# rs232.net
KiCad netlist of a schematic drawn in Altium Designer
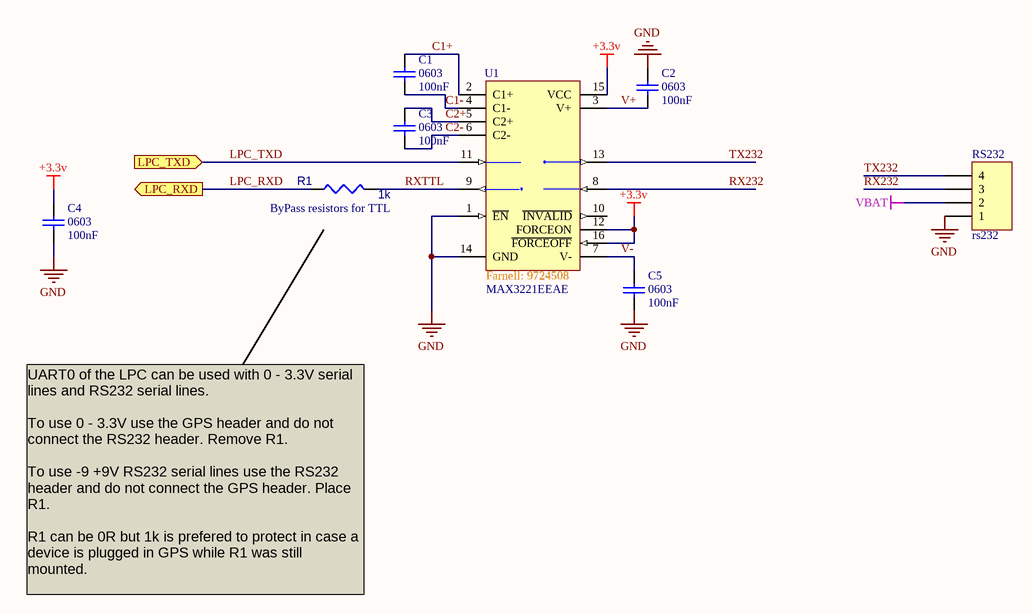
[diagram p0: rs232.SchDoc]

(export (version "E")
  (design (tool "Eeschema 10.0.6"))
  (components
    (comp (ref "C1")
      (value "0603")
      (footprint "0603")
      (description "Capacitor")
      (fields (field (name "ALTIUM_VALUE") "100nF") (field (name "PUBLISHER") "Altium Limited"))
      (libsource (lib "Miscellaneous Devices") (part "Cap"))
    )
    (comp (ref "C2")
      (value "0603")
      (footprint "0603")
      (description "Capacitor")
      (fields (field (name "ALTIUM_VALUE") "100nF") (field (name "PUBLISHER") "Altium Limited"))
      (libsource (lib "Miscellaneous Devices") (part "Cap"))
    )
    (comp (ref "C3")
      (value "0603")
      (footprint "0603")
      (description "Capacitor")
      (fields (field (name "ALTIUM_VALUE") "100nF") (field (name "PUBLISHER") "Altium Limited"))
      (libsource (lib "Miscellaneous Devices") (part "Cap"))
    )
    (comp (ref "C4")
      (value "0603")
      (footprint "0603")
      (description "Capacitor")
      (fields
        (field (name "ALTIUM_VALUE") "100nF")
        (field (name "VOLTAGE") "50V")
        (field (name "PUBLISHER") "Altium Limited")
      )
      (libsource (lib "Miscellaneous Devices") (part "Cap"))
    )
    (comp (ref "C5")
      (value "0603")
      (footprint "0603")
      (description "Capacitor")
      (fields (field (name "ALTIUM_VALUE") "100nF") (field (name "PUBLISHER") "Altium Limited"))
      (libsource (lib "Miscellaneous Devices") (part "Cap"))
    )
    (comp (ref "R1") (value "1k") (footprint "0603RES") (libsource (lib "*") (part "RES1")))
    (comp (ref "RS232")
      (value "rs232")
      (footprint "HDR4")
      (description "Header, 4-Pin")
      (fields (field (name "PUBLISHER") "Altium Limited"))
      (libsource (lib "Miscellaneous Connectors") (part "Header 4"))
    )
    (comp (ref "U1")
      (value "MAX3221EEAE")
      (footprint "SSOP16")
      (description "±15kV ESD-Protected, 1µA, 3.0V/5.5V, 250kbps, RS-232 Transceiver with AutoShutdown")
      (fields (field (name "FARNELL") "9724508") (field (name "PUBLISHER") "Altium Limited"))
      (libsource (lib "Maxim Communication Transceiver") (part "MAX3221EEAE"))
    )
  )
  (nets
    (net (code "1") (name "+3.3v") (class "Default")
      (node (ref "C4") (pin "2") (pinfunction "2_2") (pintype "passive"))
      (node (ref "U1") (pin "12") (pinfunction "FORCEON_12") (pintype "passive"))
      (node (ref "U1") (pin "15") (pinfunction "VCC_15") (pintype "power_in"))
      (node (ref "U1") (pin "16") (pinfunction "~{FORCEOFF}_16") (pintype "input"))
    )
    (net (code "2") (name "/C1+") (class "Default")
      (node (ref "C1") (pin "2") (pinfunction "2_2") (pintype "passive"))
      (node (ref "U1") (pin "2") (pinfunction "C1+_2") (pintype "passive"))
    )
    (net (code "3") (name "/C1-") (class "Default")
      (node (ref "C1") (pin "1") (pinfunction "1_1") (pintype "passive"))
      (node (ref "U1") (pin "4") (pinfunction "C1-_4") (pintype "passive"))
    )
    (net (code "4") (name "/C2+") (class "Default")
      (node (ref "C3") (pin "2") (pinfunction "2_2") (pintype "passive"))
      (node (ref "U1") (pin "5") (pinfunction "C2+_5") (pintype "passive"))
    )
    (net (code "5") (name "/C2-") (class "Default")
      (node (ref "C3") (pin "1") (pinfunction "1_1") (pintype "passive"))
      (node (ref "U1") (pin "6") (pinfunction "C2-_6") (pintype "passive"))
    )
    (net (code "6") (name "/LPC_RXD") (class "Default") (node (ref "R1") (pin "1") (pintype "passive")))
    (net (code "7") (name "/LPC_TXD") (class "Default")
      (node (ref "U1") (pin "11") (pinfunction "T1IN_11") (pintype "input"))
    )
    (net (code "8") (name "/RX232") (class "Default")
      (node (ref "RS232") (pin "3") (pinfunction "3_3") (pintype "passive"))
      (node (ref "U1") (pin "8") (pinfunction "R1IN_8") (pintype "input"))
    )
    (net (code "9") (name "/RXTTL") (class "Default")
      (node (ref "R1") (pin "2") (pintype "passive"))
      (node (ref "U1") (pin "9") (pinfunction "R1OUT_9") (pintype "output"))
    )
    (net (code "10") (name "/TX232") (class "Default")
      (node (ref "RS232") (pin "4") (pinfunction "4_4") (pintype "passive"))
      (node (ref "U1") (pin "13") (pinfunction "T1OUT_13") (pintype "output"))
    )
    (net (code "11") (name "/V+") (class "Default")
      (node (ref "C2") (pin "1") (pinfunction "1_1") (pintype "passive"))
      (node (ref "U1") (pin "3") (pinfunction "V+_3") (pintype "power_in"))
    )
    (net (code "12") (name "/V-") (class "Default")
      (node (ref "C5") (pin "2") (pinfunction "2_2") (pintype "passive"))
      (node (ref "U1") (pin "7") (pinfunction "V-_7") (pintype "power_in"))
    )
    (net (code "13") (name "GND") (class "Default")
      (node (ref "C2") (pin "2") (pinfunction "2_2") (pintype "passive"))
      (node (ref "C4") (pin "1") (pinfunction "1_1") (pintype "passive"))
      (node (ref "C5") (pin "1") (pinfunction "1_1") (pintype "passive"))
      (node (ref "RS232") (pin "1") (pinfunction "1_1") (pintype "passive"))
      (node (ref "U1") (pin "1") (pinfunction "~{EN}_1") (pintype "input"))
      (node (ref "U1") (pin "14") (pinfunction "GND_14") (pintype "power_in"))
    )
    (net (code "14") (name "VBAT") (class "Default")
      (node (ref "RS232") (pin "2") (pinfunction "2_2") (pintype "passive"))
    )
    (net (code "15") (name "unconnected-(U1-~{INVALID}-Pad10)") (class "Default")
      (node (ref "U1") (pin "10") (pinfunction "~{INVALID}_10") (pintype "output"))
    )
  )
)
